# untitled.net
KiCad netlist of a schematic drawn in EAGLE
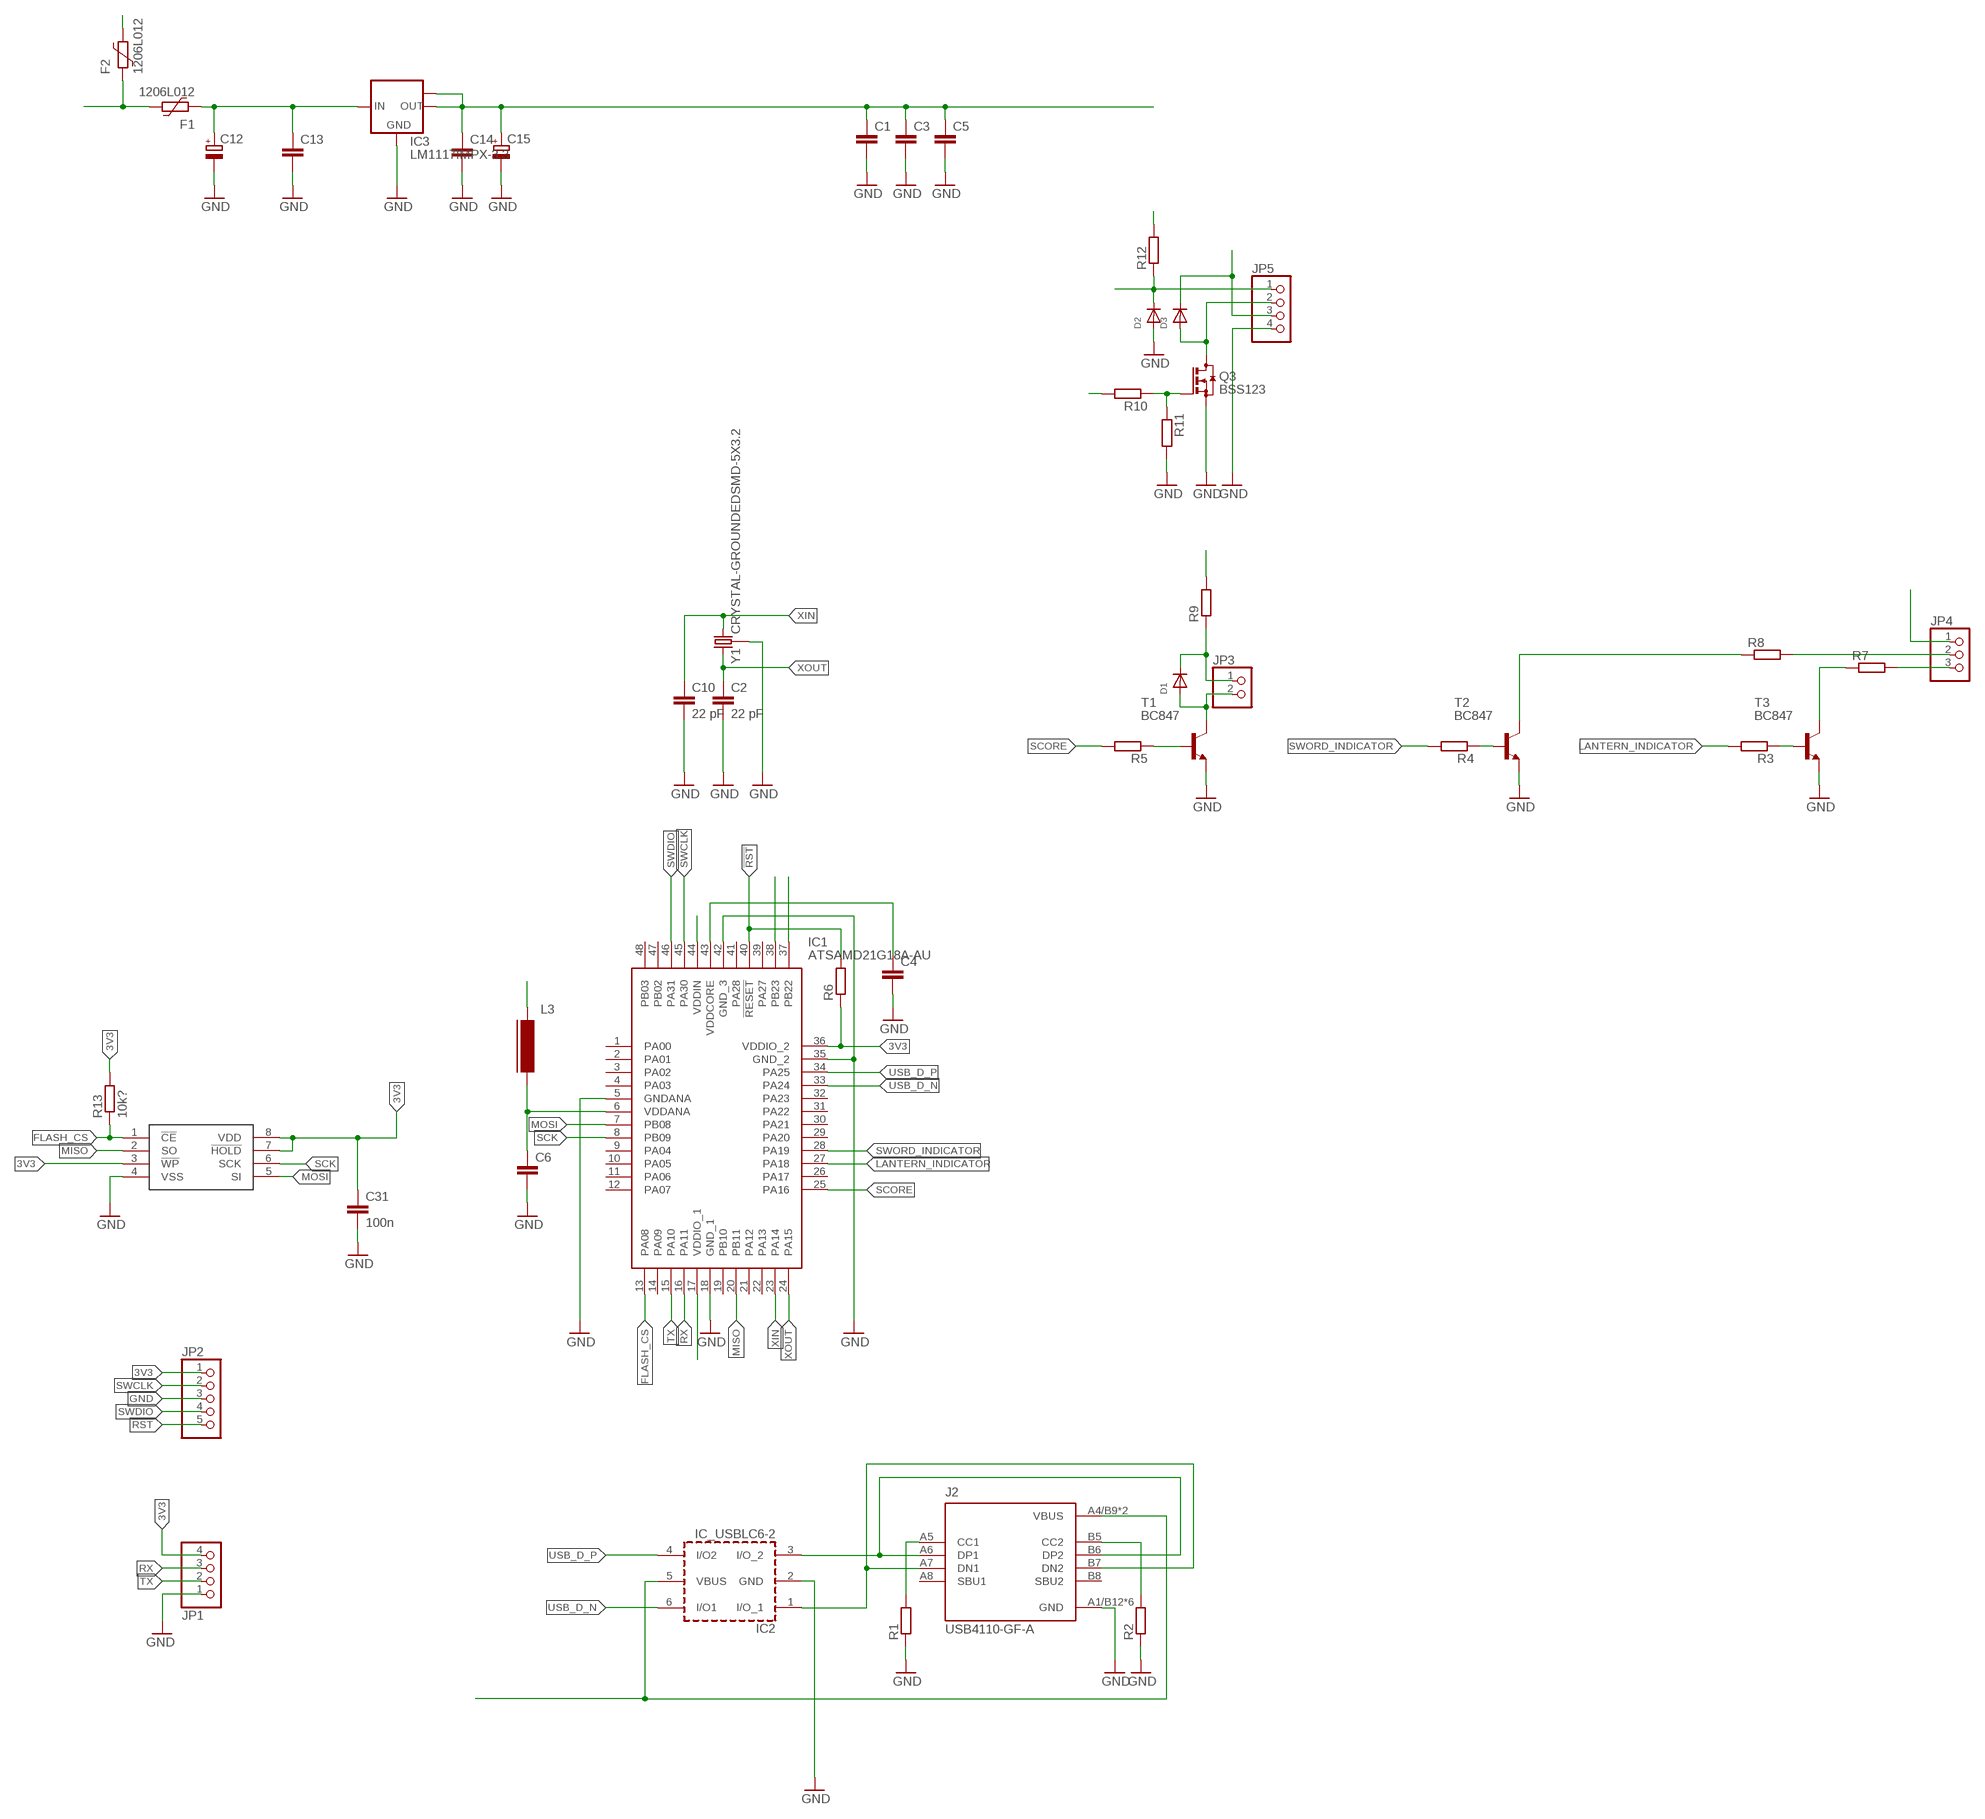
[diagram p0: schematic, sheet 1]

(export (version "E")
  (design (tool "Eeschema 10.0.6"))
  (components
    (comp (ref "C1")
      (value "C-EUC0402")
      (footprint "eagle-import:C0402")
      (libsource (lib "eagle-import") (part "C-EUC0402"))
    )
    (comp (ref "C2")
      (value "22 pF")
      (footprint "eagle-import:C0603")
      (libsource (lib "eagle-import") (part "C-EUC0603"))
    )
    (comp (ref "C3")
      (value "C-EUC0402")
      (footprint "eagle-import:C0402")
      (libsource (lib "eagle-import") (part "C-EUC0402"))
    )
    (comp (ref "C4")
      (value "C-EUC0402")
      (footprint "eagle-import:C0402")
      (libsource (lib "eagle-import") (part "C-EUC0402"))
    )
    (comp (ref "C5")
      (value "C-EUC0402")
      (footprint "eagle-import:C0402")
      (libsource (lib "eagle-import") (part "C-EUC0402"))
    )
    (comp (ref "C6")
      (value "C-EUC0402")
      (footprint "eagle-import:C0402")
      (libsource (lib "eagle-import") (part "C-EUC0402"))
    )
    (comp (ref "C10")
      (value "22 pF")
      (footprint "eagle-import:C0603")
      (libsource (lib "eagle-import") (part "C-EUC0603"))
    )
    (comp (ref "C12")
      (value "CPOL-EUSMCB")
      (footprint "eagle-import:SMC_B")
      (libsource (lib "eagle-import") (part "CPOL-EUSMCB"))
    )
    (comp (ref "C13")
      (value "C-EUC0603")
      (footprint "eagle-import:C0603")
      (libsource (lib "eagle-import") (part "C-EUC0603"))
    )
    (comp (ref "C14")
      (value "C-EUC0603")
      (footprint "eagle-import:C0603")
      (libsource (lib "eagle-import") (part "C-EUC0603"))
    )
    (comp (ref "C15")
      (value "CPOL-EUSMCB")
      (footprint "eagle-import:SMC_B")
      (libsource (lib "eagle-import") (part "CPOL-EUSMCB"))
    )
    (comp (ref "C31")
      (value "100n")
      (footprint "eagle-import:C0603")
      (libsource (lib "eagle-import") (part "C-EUC0603"))
    )
    (comp (ref "D1")
      (value "DIODESOD-323")
      (footprint "eagle-import:SOD-323")
      (libsource (lib "eagle-import") (part "DIODESOD-323"))
    )
    (comp (ref "D2")
      (value "DIODESOD-323")
      (footprint "eagle-import:SOD-323")
      (libsource (lib "eagle-import") (part "DIODESOD-323"))
    )
    (comp (ref "D3")
      (value "DIODESOD-323")
      (footprint "eagle-import:SOD-323")
      (libsource (lib "eagle-import") (part "DIODESOD-323"))
    )
    (comp (ref "F1")
      (value "1206L012")
      (footprint "eagle-import:1206L")
      (fields (field (name "MF") "Littelfuse"))
      (libsource (lib "eagle-import") (part "?1206L012"))
    )
    (comp (ref "F2")
      (value "1206L012")
      (footprint "eagle-import:1206L")
      (fields (field (name "MF") "Littelfuse"))
      (libsource (lib "eagle-import") (part "?1206L012"))
    )
    (comp (ref "IC1")
      (value "ATSAMD21G18A-AU")
      (footprint "eagle-import:QFP50P900X900X120-48N")
      (libsource (lib "eagle-import") (part "ATSAMD21G18A-AU"))
    )
    (comp (ref "IC2")
      (value "IC_USBLC6-2")
      (footprint "eagle-import:SOT-23-6L")
      (libsource (lib "eagle-import") (part "IC_USBLC6-2"))
    )
    (comp (ref "IC3")
      (value "LM1117IMPX-3.3")
      (footprint "eagle-import:SOT223")
      (libsource (lib "eagle-import") (part "LM1117IMPX-3.3"))
    )
    (comp (ref "J2")
      (value "USB4110-GF-A")
      (footprint "eagle-import:GCT_USB4110-GF-A")
      (fields (field (name "MANUFACTURER") "GCT"))
      (libsource (lib "eagle-import") (part "USB4110-GF-A"))
    )
    (comp (ref "JP1")
      (value "PINHD-1X4")
      (footprint "eagle-import:1X04")
      (libsource (lib "eagle-import") (part "PINHD-1X4"))
    )
    (comp (ref "JP2")
      (value "PINHD-1X5")
      (footprint "eagle-import:1X05")
      (libsource (lib "eagle-import") (part "PINHD-1X5"))
    )
    (comp (ref "JP3")
      (value "PINHD-1X2")
      (footprint "eagle-import:1X02")
      (libsource (lib "eagle-import") (part "PINHD-1X2"))
    )
    (comp (ref "JP4")
      (value "PINHD-1X3")
      (footprint "eagle-import:1X03")
      (libsource (lib "eagle-import") (part "PINHD-1X3"))
    )
    (comp (ref "JP5")
      (value "PINHD-1X4")
      (footprint "eagle-import:1X04")
      (libsource (lib "eagle-import") (part "PINHD-1X4"))
    )
    (comp (ref "L3")
      (value "FERRITE-0805")
      (footprint "eagle-import:FB805")
      (libsource (lib "eagle-import") (part "FERRITE-0805"))
    )
    (comp (ref "Q3")
      (value "BSS123")
      (footprint "eagle-import:SOT23")
      (libsource (lib "eagle-import") (part "BSS123"))
    )
    (comp (ref "R1")
      (value "R-EU_R0603")
      (footprint "eagle-import:R0603")
      (libsource (lib "eagle-import") (part "R-EU_R0603"))
    )
    (comp (ref "R2")
      (value "R-EU_R0603")
      (footprint "eagle-import:R0603")
      (libsource (lib "eagle-import") (part "R-EU_R0603"))
    )
    (comp (ref "R3")
      (value "R-EU_R0402")
      (footprint "eagle-import:R0402")
      (libsource (lib "eagle-import") (part "R-EU_R0402"))
    )
    (comp (ref "R4")
      (value "R-EU_R0402")
      (footprint "eagle-import:R0402")
      (libsource (lib "eagle-import") (part "R-EU_R0402"))
    )
    (comp (ref "R5")
      (value "R-EU_R0402")
      (footprint "eagle-import:R0402")
      (libsource (lib "eagle-import") (part "R-EU_R0402"))
    )
    (comp (ref "R6")
      (value "R-EU_R0603")
      (footprint "eagle-import:R0603")
      (libsource (lib "eagle-import") (part "R-EU_R0603"))
    )
    (comp (ref "R7")
      (value "R-EU_R0402")
      (footprint "eagle-import:R0402")
      (libsource (lib "eagle-import") (part "R-EU_R0402"))
    )
    (comp (ref "R8")
      (value "R-EU_R0402")
      (footprint "eagle-import:R0402")
      (libsource (lib "eagle-import") (part "R-EU_R0402"))
    )
    (comp (ref "R9")
      (value "R-EU_R0603")
      (footprint "eagle-import:R0603")
      (libsource (lib "eagle-import") (part "R-EU_R0603"))
    )
    (comp (ref "R10")
      (value "R-EU_R0402")
      (footprint "eagle-import:R0402")
      (libsource (lib "eagle-import") (part "R-EU_R0402"))
    )
    (comp (ref "R11")
      (value "R-EU_R0603")
      (footprint "eagle-import:R0603")
      (libsource (lib "eagle-import") (part "R-EU_R0603"))
    )
    (comp (ref "R12")
      (value "R-EU_R0603")
      (footprint "eagle-import:R0603")
      (libsource (lib "eagle-import") (part "R-EU_R0603"))
    )
    (comp (ref "R13")
      (value "10k?")
      (footprint "eagle-import:R0603")
      (libsource (lib "eagle-import") (part "R-EU_R0603"))
    )
    (comp (ref "T1")
      (value "BC847")
      (footprint "eagle-import:SOT23")
      (libsource (lib "eagle-import") (part "BC847"))
    )
    (comp (ref "T2")
      (value "BC847")
      (footprint "eagle-import:SOT23")
      (libsource (lib "eagle-import") (part "BC847"))
    )
    (comp (ref "T3")
      (value "BC847")
      (footprint "eagle-import:SOT23")
      (libsource (lib "eagle-import") (part "BC847"))
    )
    (comp (ref "U$2")
      (value "SST25VF016BSO8M")
      (footprint "eagle-import:SO-08M")
      (libsource (lib "eagle-import") (part "SST25VF016BSO8M"))
    )
    (comp (ref "Y1")
      (value "CRYSTAL-GROUNDEDSMD-5X3.2")
      (footprint "eagle-import:CRYSTAL-SMD-5X3.2-4PAD")
      (libsource (lib "eagle-import") (part "CRYSTAL-GROUNDEDSMD-5X3.2"))
    )
  )
  (nets
    (net (code "1") (name "/LOCK") (class "Default")
      (node (ref "IC1") (pin "37") (pinfunction "PB22_37") (pintype "bidirectional"))
      (node (ref "R10") (pin "2") (pinfunction "2_2") (pintype "passive"))
    )
    (net (code "2") (name "/LOCK_5V") (class "Default")
      (node (ref "D3") (pin "C") (pinfunction "C_C") (pintype "passive"))
      (node (ref "F2") (pin "1") (pinfunction "1_1") (pintype "passive"))
      (node (ref "JP5") (pin "3") (pinfunction "3_3") (pintype "passive"))
    )
    (net (code "3") (name "/LOCK_OPEN") (class "Default")
      (node (ref "D2") (pin "C") (pinfunction "C_C") (pintype "passive"))
      (node (ref "IC1") (pin "38") (pinfunction "PB23_38") (pintype "bidirectional"))
      (node (ref "JP5") (pin "1") (pinfunction "1_1") (pintype "passive"))
      (node (ref "R12") (pin "1") (pinfunction "1_1") (pintype "passive"))
    )
    (net (code "4") (name "/VBUS") (class "Default")
      (node (ref "F1") (pin "1") (pinfunction "1_1") (pintype "passive"))
      (node (ref "F2") (pin "2") (pinfunction "2_2") (pintype "passive"))
      (node (ref "IC2") (pin "5") (pinfunction "VBUS_5") (pintype "bidirectional"))
      (node (ref "J2") (pin "A4/B9") (pinfunction "VBUS_A4/B9") (pintype "power_in"))
      (node (ref "J2") (pin "B4/A9") (pinfunction "VBUS_B4/A9") (pintype "power_in"))
    )
    (net (code "5") (name "/~{RST}") (class "Default")
      (node (ref "IC1") (pin "40") (pinfunction "~{RESET}_40") (pintype "bidirectional"))
      (node (ref "JP2") (pin "5") (pinfunction "5_5") (pintype "passive"))
      (node (ref "R6") (pin "2") (pinfunction "2_2") (pintype "passive"))
    )
    (net (code "6") (name "3V3") (class "Default")
      (node (ref "C1") (pin "1") (pinfunction "1_1") (pintype "passive"))
      (node (ref "C14") (pin "1") (pinfunction "1_1") (pintype "passive"))
      (node (ref "C15") (pin "+") (pinfunction "+_+") (pintype "passive"))
      (node (ref "C3") (pin "1") (pinfunction "1_1") (pintype "passive"))
      (node (ref "C31") (pin "1") (pinfunction "1_1") (pintype "passive"))
      (node (ref "C5") (pin "1") (pinfunction "1_1") (pintype "passive"))
      (node (ref "IC1") (pin "17") (pinfunction "VDDIO_1_17") (pintype "bidirectional"))
      (node (ref "IC1") (pin "36") (pinfunction "VDDIO_2_36") (pintype "bidirectional"))
      (node (ref "IC1") (pin "44") (pinfunction "VDDIN_44") (pintype "bidirectional"))
      (node (ref "IC3") (pin "2") (pinfunction "OUT_2") (pintype "passive"))
      (node (ref "IC3") (pin "TAB") (pinfunction "OUT1_TAB") (pintype "passive"))
      (node (ref "JP1") (pin "4") (pinfunction "4_4") (pintype "passive"))
      (node (ref "JP2") (pin "1") (pinfunction "1_1") (pintype "passive"))
      (node (ref "JP4") (pin "1") (pinfunction "1_1") (pintype "passive"))
      (node (ref "L3") (pin "1") (pinfunction "1_1") (pintype "passive"))
      (node (ref "R12") (pin "2") (pinfunction "2_2") (pintype "passive"))
      (node (ref "R13") (pin "2") (pinfunction "2_2") (pintype "passive"))
      (node (ref "R6") (pin "1") (pinfunction "1_1") (pintype "passive"))
      (node (ref "R9") (pin "2") (pinfunction "2_2") (pintype "passive"))
      (node (ref "U$2") (pin "3") (pinfunction "~{WP}_3") (pintype "bidirectional"))
      (node (ref "U$2") (pin "7") (pinfunction "~{HOLD}_7") (pintype "bidirectional"))
      (node (ref "U$2") (pin "8") (pinfunction "VDD_8") (pintype "bidirectional"))
    )
    (net (code "7") (name "FLASH_CS") (class "Default")
      (node (ref "IC1") (pin "13") (pinfunction "PA08_13") (pintype "bidirectional"))
      (node (ref "R13") (pin "1") (pinfunction "1_1") (pintype "passive"))
      (node (ref "U$2") (pin "1") (pinfunction "~{CE}_1") (pintype "bidirectional"))
    )
    (net (code "8") (name "GND") (class "Default")
      (node (ref "C1") (pin "2") (pinfunction "2_2") (pintype "passive"))
      (node (ref "C10") (pin "2") (pinfunction "2_2") (pintype "passive"))
      (node (ref "C12") (pin "-") (pinfunction "-_-") (pintype "passive"))
      (node (ref "C13") (pin "2") (pinfunction "2_2") (pintype "passive"))
      (node (ref "C14") (pin "2") (pinfunction "2_2") (pintype "passive"))
      (node (ref "C15") (pin "-") (pinfunction "-_-") (pintype "passive"))
      (node (ref "C2") (pin "2") (pinfunction "2_2") (pintype "passive"))
      (node (ref "C3") (pin "2") (pinfunction "2_2") (pintype "passive"))
      (node (ref "C31") (pin "2") (pinfunction "2_2") (pintype "passive"))
      (node (ref "C4") (pin "2") (pinfunction "2_2") (pintype "passive"))
      (node (ref "C5") (pin "2") (pinfunction "2_2") (pintype "passive"))
      (node (ref "C6") (pin "2") (pinfunction "2_2") (pintype "passive"))
      (node (ref "D2") (pin "A") (pinfunction "A_A") (pintype "passive"))
      (node (ref "IC1") (pin "18") (pinfunction "GND_1_18") (pintype "bidirectional"))
      (node (ref "IC1") (pin "35") (pinfunction "GND_2_35") (pintype "bidirectional"))
      (node (ref "IC1") (pin "42") (pinfunction "GND_3_42") (pintype "bidirectional"))
      (node (ref "IC1") (pin "5") (pinfunction "GNDANA_5") (pintype "bidirectional"))
      (node (ref "IC2") (pin "2") (pinfunction "GND_2") (pintype "bidirectional"))
      (node (ref "IC3") (pin "1") (pinfunction "GND_1") (pintype "input"))
      (node (ref "J2") (pin "A1/B12") (pinfunction "GND_A1/B12") (pintype "power_in"))
      (node (ref "J2") (pin "B1/A12") (pinfunction "GND_B1/A12") (pintype "power_in"))
      (node (ref "J2") (pin "S1") (pinfunction "GND_S1") (pintype "power_in"))
      (node (ref "J2") (pin "S2") (pinfunction "GND_S2") (pintype "power_in"))
      (node (ref "J2") (pin "S3") (pinfunction "GND_S3") (pintype "power_in"))
      (node (ref "J2") (pin "S4") (pinfunction "GND_S4") (pintype "power_in"))
      (node (ref "JP1") (pin "1") (pinfunction "1_1") (pintype "passive"))
      (node (ref "JP2") (pin "3") (pinfunction "3_3") (pintype "passive"))
      (node (ref "JP5") (pin "4") (pinfunction "4_4") (pintype "passive"))
      (node (ref "Q3") (pin "2") (pinfunction "S_2") (pintype "passive"))
      (node (ref "R1") (pin "1") (pinfunction "1_1") (pintype "passive"))
      (node (ref "R11") (pin "2") (pinfunction "2_2") (pintype "passive"))
      (node (ref "R2") (pin "1") (pinfunction "1_1") (pintype "passive"))
      (node (ref "T1") (pin "2") (pinfunction "E_2") (pintype "passive"))
      (node (ref "T2") (pin "2") (pinfunction "E_2") (pintype "passive"))
      (node (ref "T3") (pin "2") (pinfunction "E_2") (pintype "passive"))
      (node (ref "U$2") (pin "4") (pinfunction "VSS_4") (pintype "bidirectional"))
      (node (ref "Y1") (pin "2") (pinfunction "3_2") (pintype "passive"))
      (node (ref "Y1") (pin "4") (pinfunction "3_4") (pintype "passive"))
    )
    (net (code "9") (name "LANTERN_INDICATOR") (class "Default")
      (node (ref "IC1") (pin "27") (pinfunction "PA18_27") (pintype "bidirectional"))
      (node (ref "R3") (pin "2") (pinfunction "2_2") (pintype "passive"))
    )
    (net (code "10") (name "MISO") (class "Default")
      (node (ref "IC1") (pin "20") (pinfunction "PB11_20") (pintype "bidirectional"))
      (node (ref "U$2") (pin "2") (pinfunction "SO_2") (pintype "bidirectional"))
    )
    (net (code "11") (name "MOSI") (class "Default")
      (node (ref "IC1") (pin "7") (pinfunction "PB08_7") (pintype "bidirectional"))
      (node (ref "U$2") (pin "5") (pinfunction "SI_5") (pintype "bidirectional"))
    )
    (net (code "12") (name "Net-(D1-PadC)") (class "Default")
      (node (ref "D1") (pin "C") (pinfunction "C_C") (pintype "passive"))
      (node (ref "JP3") (pin "1") (pinfunction "1_1") (pintype "passive"))
      (node (ref "R9") (pin "1") (pinfunction "1_1") (pintype "passive"))
    )
    (net (code "13") (name "Net-(IC1-VDDANA)") (class "Default")
      (node (ref "C6") (pin "1") (pinfunction "1_1") (pintype "passive"))
      (node (ref "IC1") (pin "6") (pinfunction "VDDANA_6") (pintype "bidirectional"))
      (node (ref "L3") (pin "2") (pinfunction "2_2") (pintype "passive"))
    )
    (net (code "14") (name "Net-(IC1-VDDCORE)") (class "Default")
      (node (ref "C4") (pin "1") (pinfunction "1_1") (pintype "passive"))
      (node (ref "IC1") (pin "43") (pinfunction "VDDCORE_43") (pintype "bidirectional"))
    )
    (net (code "15") (name "Net-(IC2-I{slash}O_1)") (class "Default")
      (node (ref "IC2") (pin "1") (pinfunction "I/O_1_1") (pintype "bidirectional"))
      (node (ref "J2") (pin "A7") (pinfunction "DN1_A7") (pintype "bidirectional"))
      (node (ref "J2") (pin "B7") (pinfunction "DN2_B7") (pintype "bidirectional"))
    )
    (net (code "16") (name "Net-(IC2-I{slash}O_2)") (class "Default")
      (node (ref "IC2") (pin "3") (pinfunction "I/O_2_3") (pintype "bidirectional"))
      (node (ref "J2") (pin "A6") (pinfunction "DP1_A6") (pintype "bidirectional"))
      (node (ref "J2") (pin "B6") (pinfunction "DP2_B6") (pintype "bidirectional"))
    )
    (net (code "17") (name "Net-(IC3-IN)") (class "Default")
      (node (ref "C12") (pin "+") (pinfunction "+_+") (pintype "passive"))
      (node (ref "C13") (pin "1") (pinfunction "1_1") (pintype "passive"))
      (node (ref "F1") (pin "2") (pinfunction "2_2") (pintype "passive"))
      (node (ref "IC3") (pin "3") (pinfunction "IN_3") (pintype "input"))
    )
    (net (code "18") (name "Net-(J2-CC1)") (class "Default")
      (node (ref "J2") (pin "A5") (pinfunction "CC1_A5") (pintype "bidirectional"))
      (node (ref "R1") (pin "2") (pinfunction "2_2") (pintype "passive"))
    )
    (net (code "19") (name "Net-(J2-CC2)") (class "Default")
      (node (ref "J2") (pin "B5") (pinfunction "CC2_B5") (pintype "bidirectional"))
      (node (ref "R2") (pin "2") (pinfunction "2_2") (pintype "passive"))
    )
    (net (code "20") (name "Net-(JP4-Pad2)") (class "Default")
      (node (ref "JP4") (pin "2") (pinfunction "2_2") (pintype "passive"))
      (node (ref "R8") (pin "2") (pinfunction "2_2") (pintype "passive"))
    )
    (net (code "21") (name "Net-(JP4-Pad3)") (class "Default")
      (node (ref "JP4") (pin "3") (pinfunction "3_3") (pintype "passive"))
      (node (ref "R7") (pin "2") (pinfunction "2_2") (pintype "passive"))
    )
    (net (code "22") (name "Net-(Q3-D)") (class "Default")
      (node (ref "D3") (pin "A") (pinfunction "A_A") (pintype "passive"))
      (node (ref "JP5") (pin "2") (pinfunction "2_2") (pintype "passive"))
      (node (ref "Q3") (pin "3") (pinfunction "D_3") (pintype "passive"))
    )
    (net (code "23") (name "Net-(Q3-G)") (class "Default")
      (node (ref "Q3") (pin "1") (pinfunction "G_1") (pintype "passive"))
      (node (ref "R10") (pin "1") (pinfunction "1_1") (pintype "passive"))
      (node (ref "R11") (pin "1") (pinfunction "1_1") (pintype "passive"))
    )
    (net (code "24") (name "Net-(T1-B)") (class "Default")
      (node (ref "R5") (pin "1") (pinfunction "1_1") (pintype "passive"))
      (node (ref "T1") (pin "1") (pinfunction "B_1") (pintype "passive"))
    )
    (net (code "25") (name "Net-(T1-C)") (class "Default")
      (node (ref "D1") (pin "A") (pinfunction "A_A") (pintype "passive"))
      (node (ref "JP3") (pin "2") (pinfunction "2_2") (pintype "passive"))
      (node (ref "T1") (pin "3") (pinfunction "C_3") (pintype "passive"))
    )
    (net (code "26") (name "Net-(T2-B)") (class "Default")
      (node (ref "R4") (pin "1") (pinfunction "1_1") (pintype "passive"))
      (node (ref "T2") (pin "1") (pinfunction "B_1") (pintype "passive"))
    )
    (net (code "27") (name "Net-(T2-C)") (class "Default")
      (node (ref "R8") (pin "1") (pinfunction "1_1") (pintype "passive"))
      (node (ref "T2") (pin "3") (pinfunction "C_3") (pintype "passive"))
    )
    (net (code "28") (name "Net-(T3-B)") (class "Default")
      (node (ref "R3") (pin "1") (pinfunction "1_1") (pintype "passive"))
      (node (ref "T3") (pin "1") (pinfunction "B_1") (pintype "passive"))
    )
    (net (code "29") (name "Net-(T3-C)") (class "Default")
      (node (ref "R7") (pin "1") (pinfunction "1_1") (pintype "passive"))
      (node (ref "T3") (pin "3") (pinfunction "C_3") (pintype "passive"))
    )
    (net (code "30") (name "RX") (class "Default")
      (node (ref "IC1") (pin "16") (pinfunction "PA11_16") (pintype "bidirectional"))
      (node (ref "JP1") (pin "3") (pinfunction "3_3") (pintype "passive"))
    )
    (net (code "31") (name "SCK") (class "Default")
      (node (ref "IC1") (pin "8") (pinfunction "PB09_8") (pintype "bidirectional"))
      (node (ref "U$2") (pin "6") (pinfunction "SCK_6") (pintype "bidirectional"))
    )
    (net (code "32") (name "SCORE") (class "Default")
      (node (ref "IC1") (pin "25") (pinfunction "PA16_25") (pintype "bidirectional"))
      (node (ref "R5") (pin "2") (pinfunction "2_2") (pintype "passive"))
    )
    (net (code "33") (name "SWCLK") (class "Default")
      (node (ref "IC1") (pin "45") (pinfunction "PA30_45") (pintype "bidirectional"))
      (node (ref "JP2") (pin "2") (pinfunction "2_2") (pintype "passive"))
    )
    (net (code "34") (name "SWDIO") (class "Default")
      (node (ref "IC1") (pin "46") (pinfunction "PA31_46") (pintype "bidirectional"))
      (node (ref "JP2") (pin "4") (pinfunction "4_4") (pintype "passive"))
    )
    (net (code "35") (name "SWORD_INDICATOR") (class "Default")
      (node (ref "IC1") (pin "28") (pinfunction "PA19_28") (pintype "bidirectional"))
      (node (ref "R4") (pin "2") (pinfunction "2_2") (pintype "passive"))
    )
    (net (code "36") (name "TX") (class "Default")
      (node (ref "IC1") (pin "15") (pinfunction "PA10_15") (pintype "bidirectional"))
      (node (ref "JP1") (pin "2") (pinfunction "2_2") (pintype "passive"))
    )
    (net (code "37") (name "USB_D_N") (class "Default")
      (node (ref "IC1") (pin "33") (pinfunction "PA24_33") (pintype "bidirectional"))
      (node (ref "IC2") (pin "6") (pinfunction "I/O1_6") (pintype "bidirectional"))
    )
    (net (code "38") (name "USB_D_P") (class "Default")
      (node (ref "IC1") (pin "34") (pinfunction "PA25_34") (pintype "bidirectional"))
      (node (ref "IC2") (pin "4") (pinfunction "I/O2_4") (pintype "bidirectional"))
    )
    (net (code "39") (name "XIN") (class "Default")
      (node (ref "C10") (pin "1") (pinfunction "1_1") (pintype "passive"))
      (node (ref "IC1") (pin "23") (pinfunction "PA14_23") (pintype "bidirectional"))
      (node (ref "Y1") (pin "1") (pinfunction "2_1") (pintype "passive"))
    )
    (net (code "40") (name "XOUT") (class "Default")
      (node (ref "C2") (pin "1") (pinfunction "1_1") (pintype "passive"))
      (node (ref "IC1") (pin "24") (pinfunction "PA15_24") (pintype "bidirectional"))
      (node (ref "Y1") (pin "3") (pinfunction "1_3") (pintype "passive"))
    )
    (net (code "41") (name "unconnected-(IC1-PA00-Pad1)") (class "Default")
      (node (ref "IC1") (pin "1") (pinfunction "PA00_1") (pintype "bidirectional"))
    )
    (net (code "42") (name "unconnected-(IC1-PA01-Pad2)") (class "Default")
      (node (ref "IC1") (pin "2") (pinfunction "PA01_2") (pintype "bidirectional"))
    )
    (net (code "43") (name "unconnected-(IC1-PA02-Pad3)") (class "Default")
      (node (ref "IC1") (pin "3") (pinfunction "PA02_3") (pintype "bidirectional"))
    )
    (net (code "44") (name "unconnected-(IC1-PA03-Pad4)") (class "Default")
      (node (ref "IC1") (pin "4") (pinfunction "PA03_4") (pintype "bidirectional"))
    )
    (net (code "45") (name "unconnected-(IC1-PA04-Pad9)") (class "Default")
      (node (ref "IC1") (pin "9") (pinfunction "PA04_9") (pintype "bidirectional"))
    )
    (net (code "46") (name "unconnected-(IC1-PA05-Pad10)") (class "Default")
      (node (ref "IC1") (pin "10") (pinfunction "PA05_10") (pintype "bidirectional"))
    )
    (net (code "47") (name "unconnected-(IC1-PA06-Pad11)") (class "Default")
      (node (ref "IC1") (pin "11") (pinfunction "PA06_11") (pintype "bidirectional"))
    )
    (net (code "48") (name "unconnected-(IC1-PA07-Pad12)") (class "Default")
      (node (ref "IC1") (pin "12") (pinfunction "PA07_12") (pintype "bidirectional"))
    )
    (net (code "49") (name "unconnected-(IC1-PA09-Pad14)") (class "Default")
      (node (ref "IC1") (pin "14") (pinfunction "PA09_14") (pintype "bidirectional"))
    )
    (net (code "50") (name "unconnected-(IC1-PA12-Pad21)") (class "Default")
      (node (ref "IC1") (pin "21") (pinfunction "PA12_21") (pintype "bidirectional"))
    )
    (net (code "51") (name "unconnected-(IC1-PA13-Pad22)") (class "Default")
      (node (ref "IC1") (pin "22") (pinfunction "PA13_22") (pintype "bidirectional"))
    )
    (net (code "52") (name "unconnected-(IC1-PA17-Pad26)") (class "Default")
      (node (ref "IC1") (pin "26") (pinfunction "PA17_26") (pintype "bidirectional"))
    )
    (net (code "53") (name "unconnected-(IC1-PA20-Pad29)") (class "Default")
      (node (ref "IC1") (pin "29") (pinfunction "PA20_29") (pintype "bidirectional"))
    )
    (net (code "54") (name "unconnected-(IC1-PA21-Pad30)") (class "Default")
      (node (ref "IC1") (pin "30") (pinfunction "PA21_30") (pintype "bidirectional"))
    )
    (net (code "55") (name "unconnected-(IC1-PA22-Pad31)") (class "Default")
      (node (ref "IC1") (pin "31") (pinfunction "PA22_31") (pintype "bidirectional"))
    )
    (net (code "56") (name "unconnected-(IC1-PA23-Pad32)") (class "Default")
      (node (ref "IC1") (pin "32") (pinfunction "PA23_32") (pintype "bidirectional"))
    )
    (net (code "57") (name "unconnected-(IC1-PA27-Pad39)") (class "Default")
      (node (ref "IC1") (pin "39") (pinfunction "PA27_39") (pintype "bidirectional"))
    )
    (net (code "58") (name "unconnected-(IC1-PA28-Pad41)") (class "Default")
      (node (ref "IC1") (pin "41") (pinfunction "PA28_41") (pintype "bidirectional"))
    )
    (net (code "59") (name "unconnected-(IC1-PB02-Pad47)") (class "Default")
      (node (ref "IC1") (pin "47") (pinfunction "PB02_47") (pintype "bidirectional"))
    )
    (net (code "60") (name "unconnected-(IC1-PB03-Pad48)") (class "Default")
      (node (ref "IC1") (pin "48") (pinfunction "PB03_48") (pintype "bidirectional"))
    )
    (net (code "61") (name "unconnected-(IC1-PB10-Pad19)") (class "Default")
      (node (ref "IC1") (pin "19") (pinfunction "PB10_19") (pintype "bidirectional"))
    )
    (net (code "62") (name "unconnected-(J2-SBU1-PadA8)") (class "Default")
      (node (ref "J2") (pin "A8") (pinfunction "SBU1_A8") (pintype "bidirectional"))
    )
    (net (code "63") (name "unconnected-(J2-SBU2-PadB8)") (class "Default")
      (node (ref "J2") (pin "B8") (pinfunction "SBU2_B8") (pintype "bidirectional"))
    )
  )
)
